# SebastianAltiumClassSCH.net
KiCad netlist of a schematic drawn in Altium Designer
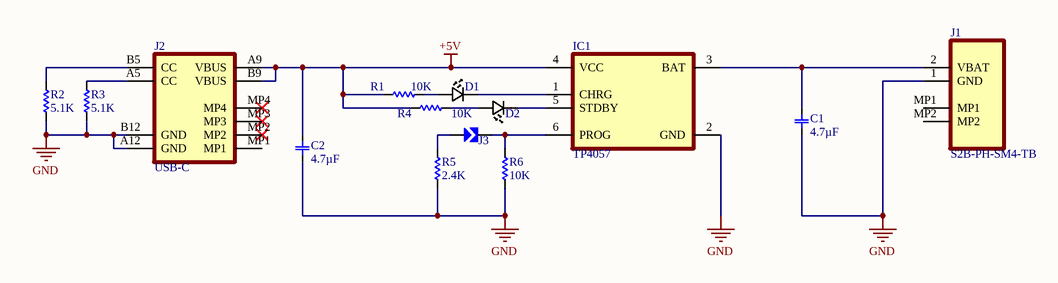
[diagram p0: SebastianAltiumClassSCH.SchDoc]

(export (version "E")
  (design (tool "Eeschema 10.0.6"))
  (components
    (comp (ref "C1")
      (value "4.7uF")
      (footprint "SebkaPcb:CAP0603")
      (description "4.7uF Capacitor, 0603")
      (fields (field (name "CAPACITANCE") "4.7µF"))
      (libsource (lib "SebastianAltiumClass") (part "Capacitor_4.7uF"))
    )
    (comp (ref "C2")
      (value "4.7uF")
      (footprint "SebkaPcb:CAP0603")
      (description "4.7uF Capacitor, 0603")
      (fields (field (name "CAPACITANCE") "4.7µF"))
      (libsource (lib "SebastianAltiumClass") (part "Capacitor_4.7uF"))
    )
    (comp (ref "D1")
      (value "LED")
      (footprint "SebastianAltiumClass:LED0603")
      (description "LED, 0603")
      (libsource (lib "SebastianAltiumClass") (part "LED"))
    )
    (comp (ref "D2")
      (value "LED")
      (footprint "SebastianAltiumClass:LED0603")
      (description "LED, 0603")
      (libsource (lib "SebastianAltiumClass") (part "LED"))
    )
    (comp (ref "IC1")
      (value "TP4057")
      (footprint "SebastianAltiumClass:SOT95P280X125-6N")
      (description "Lithium-Ion Battery Charger, 500mA max")
      (fields (field (name "MANUFACTURER_PART_NUMBER") "TP4057-42-SOT26-R"))
      (libsource (lib "SebastianAltiumClass") (part "TP4057"))
    )
    (comp (ref "J1")
      (value "S2B-PH-SM4-TB")
      (footprint "SebastianAltiumClass:S2BPHSM4TBLFSN")
      (description "DigiKey Part - \r\nPH Series 2 pin connector - \r\nS2B-PH-SM4-TB")
      (fields (field (name "MANUFACTURER_PART_NUMBER") "S2B-PH-SM4-TB(LF)(SN)"))
      (libsource (lib "SebastianAltiumClass") (part "S2B-PH-SM4-TB"))
    )
    (comp (ref "J2")
      (value "USB-C")
      (footprint "SebastianAltiumClass:USBC")
      (description "USB-C Port, Power Only")
      (libsource (lib "SebastianAltiumClass") (part "USB-C"))
    )
    (comp (ref "J3")
      (value "SOLDERBRIDGE")
      (footprint "SebastianAltiumClass:SOLDERBRIDGE")
      (libsource (lib "SebastianAltiumClass") (part "SOLDERBRIDGE"))
    )
    (comp (ref "R1")
      (value "10K")
      (footprint "SebastianAltiumClass:RES0603")
      (description "10K Resistor, 0603")
      (fields (field (name "RESISTANCE") "10K"))
      (libsource (lib "SebastianAltiumClass") (part "Resistor_10K"))
    )
    (comp (ref "R2")
      (value "5.1K")
      (footprint "SebastianAltiumClass:RES0603")
      (description "5.1K Resistor, 0603")
      (fields (field (name "RESISTANCE") "5.1K"))
      (libsource (lib "SebastianAltiumClass") (part "Resistor_5.1K"))
    )
    (comp (ref "R3")
      (value "5.1K")
      (footprint "SebastianAltiumClass:RES0603")
      (description "5.1K Resistor, 0603")
      (fields (field (name "RESISTANCE") "5.1K"))
      (libsource (lib "SebastianAltiumClass") (part "Resistor_5.1K"))
    )
    (comp (ref "R4")
      (value "10K")
      (footprint "SebastianAltiumClass:RES0603")
      (description "10K Resistor, 0603")
      (fields (field (name "RESISTANCE") "10K"))
      (libsource (lib "SebastianAltiumClass") (part "Resistor_10K"))
    )
    (comp (ref "R5")
      (value "2.4K")
      (footprint "SebastianAltiumClass:RES0603")
      (description "2.4K Resistor, 0603")
      (fields (field (name "RESISTANCE") "2.4K"))
      (libsource (lib "SebastianAltiumClass") (part "Resistor_2K"))
    )
    (comp (ref "R6")
      (value "10K")
      (footprint "SebastianAltiumClass:RES0603")
      (description "10K Resistor, 0603")
      (fields (field (name "RESISTANCE") "10K"))
      (libsource (lib "SebastianAltiumClass") (part "Resistor_10K"))
    )
  )
  (nets
    (net (code "1") (name "+5V") (class "Default")
      (node (ref "C2") (pin "2") (pinfunction "2_2") (pintype "passive"))
      (node (ref "IC1") (pin "4") (pinfunction "VCC_4") (pintype "passive"))
      (node (ref "J2") (pin "A9") (pinfunction "VBUS_A9") (pintype "passive"))
      (node (ref "J2") (pin "B9") (pinfunction "VBUS_B9") (pintype "passive"))
      (node (ref "R1") (pin "1") (pinfunction "1_1") (pintype "passive"))
      (node (ref "R4") (pin "1") (pinfunction "1_1") (pintype "passive"))
    )
    (net (code "2") (name "GND") (class "Default")
      (node (ref "C1") (pin "1") (pinfunction "1_1") (pintype "passive"))
      (node (ref "C2") (pin "1") (pinfunction "1_1") (pintype "passive"))
      (node (ref "IC1") (pin "2") (pinfunction "GND_2") (pintype "passive"))
      (node (ref "J1") (pin "1") (pinfunction "GND_1") (pintype "passive"))
      (node (ref "J2") (pin "A12") (pinfunction "GND_A12") (pintype "passive"))
      (node (ref "J2") (pin "B12") (pinfunction "GND_B12") (pintype "passive"))
      (node (ref "R2") (pin "1") (pinfunction "1_1") (pintype "passive"))
      (node (ref "R3") (pin "1") (pinfunction "1_1") (pintype "passive"))
      (node (ref "R5") (pin "1") (pinfunction "1_1") (pintype "passive"))
      (node (ref "R6") (pin "1") (pinfunction "1_1") (pintype "passive"))
    )
    (net (code "3") (name "Net-(D1-A)") (class "Default")
      (node (ref "D1") (pin "2") (pinfunction "A_2") (pintype "passive"))
      (node (ref "R1") (pin "2") (pinfunction "2_2") (pintype "passive"))
    )
    (net (code "4") (name "Net-(D1-K)") (class "Default")
      (node (ref "D1") (pin "1") (pinfunction "K_1") (pintype "passive"))
      (node (ref "IC1") (pin "1") (pinfunction "CHRG_1") (pintype "passive"))
    )
    (net (code "5") (name "Net-(D2-A)") (class "Default")
      (node (ref "D2") (pin "2") (pinfunction "A_2") (pintype "passive"))
      (node (ref "R4") (pin "2") (pinfunction "2_2") (pintype "passive"))
    )
    (net (code "6") (name "Net-(D2-K)") (class "Default")
      (node (ref "D2") (pin "1") (pinfunction "K_1") (pintype "passive"))
      (node (ref "IC1") (pin "5") (pinfunction "STDBY_5") (pintype "passive"))
    )
    (net (code "7") (name "Net-(IC1-BAT)") (class "Default")
      (node (ref "C1") (pin "2") (pinfunction "2_2") (pintype "passive"))
      (node (ref "IC1") (pin "3") (pinfunction "BAT_3") (pintype "passive"))
      (node (ref "J1") (pin "2") (pinfunction "VBAT_2") (pintype "passive"))
    )
    (net (code "8") (name "Net-(IC1-PROG)") (class "Default")
      (node (ref "IC1") (pin "6") (pinfunction "PROG_6") (pintype "passive"))
      (node (ref "J3") (pin "2") (pinfunction "2_2") (pintype "passive"))
      (node (ref "R6") (pin "2") (pinfunction "2_2") (pintype "passive"))
    )
    (net (code "9") (name "Net-(J2-CC-PadA5)") (class "Default")
      (node (ref "J2") (pin "A5") (pinfunction "CC_A5") (pintype "passive"))
      (node (ref "R3") (pin "2") (pinfunction "2_2") (pintype "passive"))
    )
    (net (code "10") (name "Net-(J2-CC-PadB5)") (class "Default")
      (node (ref "J2") (pin "B5") (pinfunction "CC_B5") (pintype "passive"))
      (node (ref "R2") (pin "2") (pinfunction "2_2") (pintype "passive"))
    )
    (net (code "11") (name "Net-(J3-Pad1)") (class "Default")
      (node (ref "J3") (pin "1") (pinfunction "1_1") (pintype "passive"))
      (node (ref "R5") (pin "2") (pinfunction "2_2") (pintype "passive"))
    )
    (net (code "12") (name "unconnected-(J1-PadMP1)") (class "Default")
      (node (ref "J1") (pin "MP1") (pinfunction "MP1_MP1") (pintype "passive"))
    )
    (net (code "13") (name "unconnected-(J1-PadMP2)") (class "Default")
      (node (ref "J1") (pin "MP2") (pinfunction "MP2_MP2") (pintype "passive"))
    )
    (net (code "14") (name "unconnected-(J2-PadMP1)") (class "Default")
      (node (ref "J2") (pin "MP1") (pinfunction "MP1_MP1") (pintype "passive"))
    )
    (net (code "15") (name "unconnected-(J2-PadMP2)") (class "Default")
      (node (ref "J2") (pin "MP2") (pinfunction "MP2_MP2") (pintype "passive+no_connect"))
    )
    (net (code "16") (name "unconnected-(J2-PadMP3)") (class "Default")
      (node (ref "J2") (pin "MP3") (pinfunction "MP3_MP3") (pintype "passive+no_connect"))
    )
    (net (code "17") (name "unconnected-(J2-PadMP4)") (class "Default")
      (node (ref "J2") (pin "MP4") (pinfunction "MP4_MP4") (pintype "passive+no_connect"))
    )
  )
)
